# Sheet3.net
KiCad netlist of a schematic drawn in Altium Designer
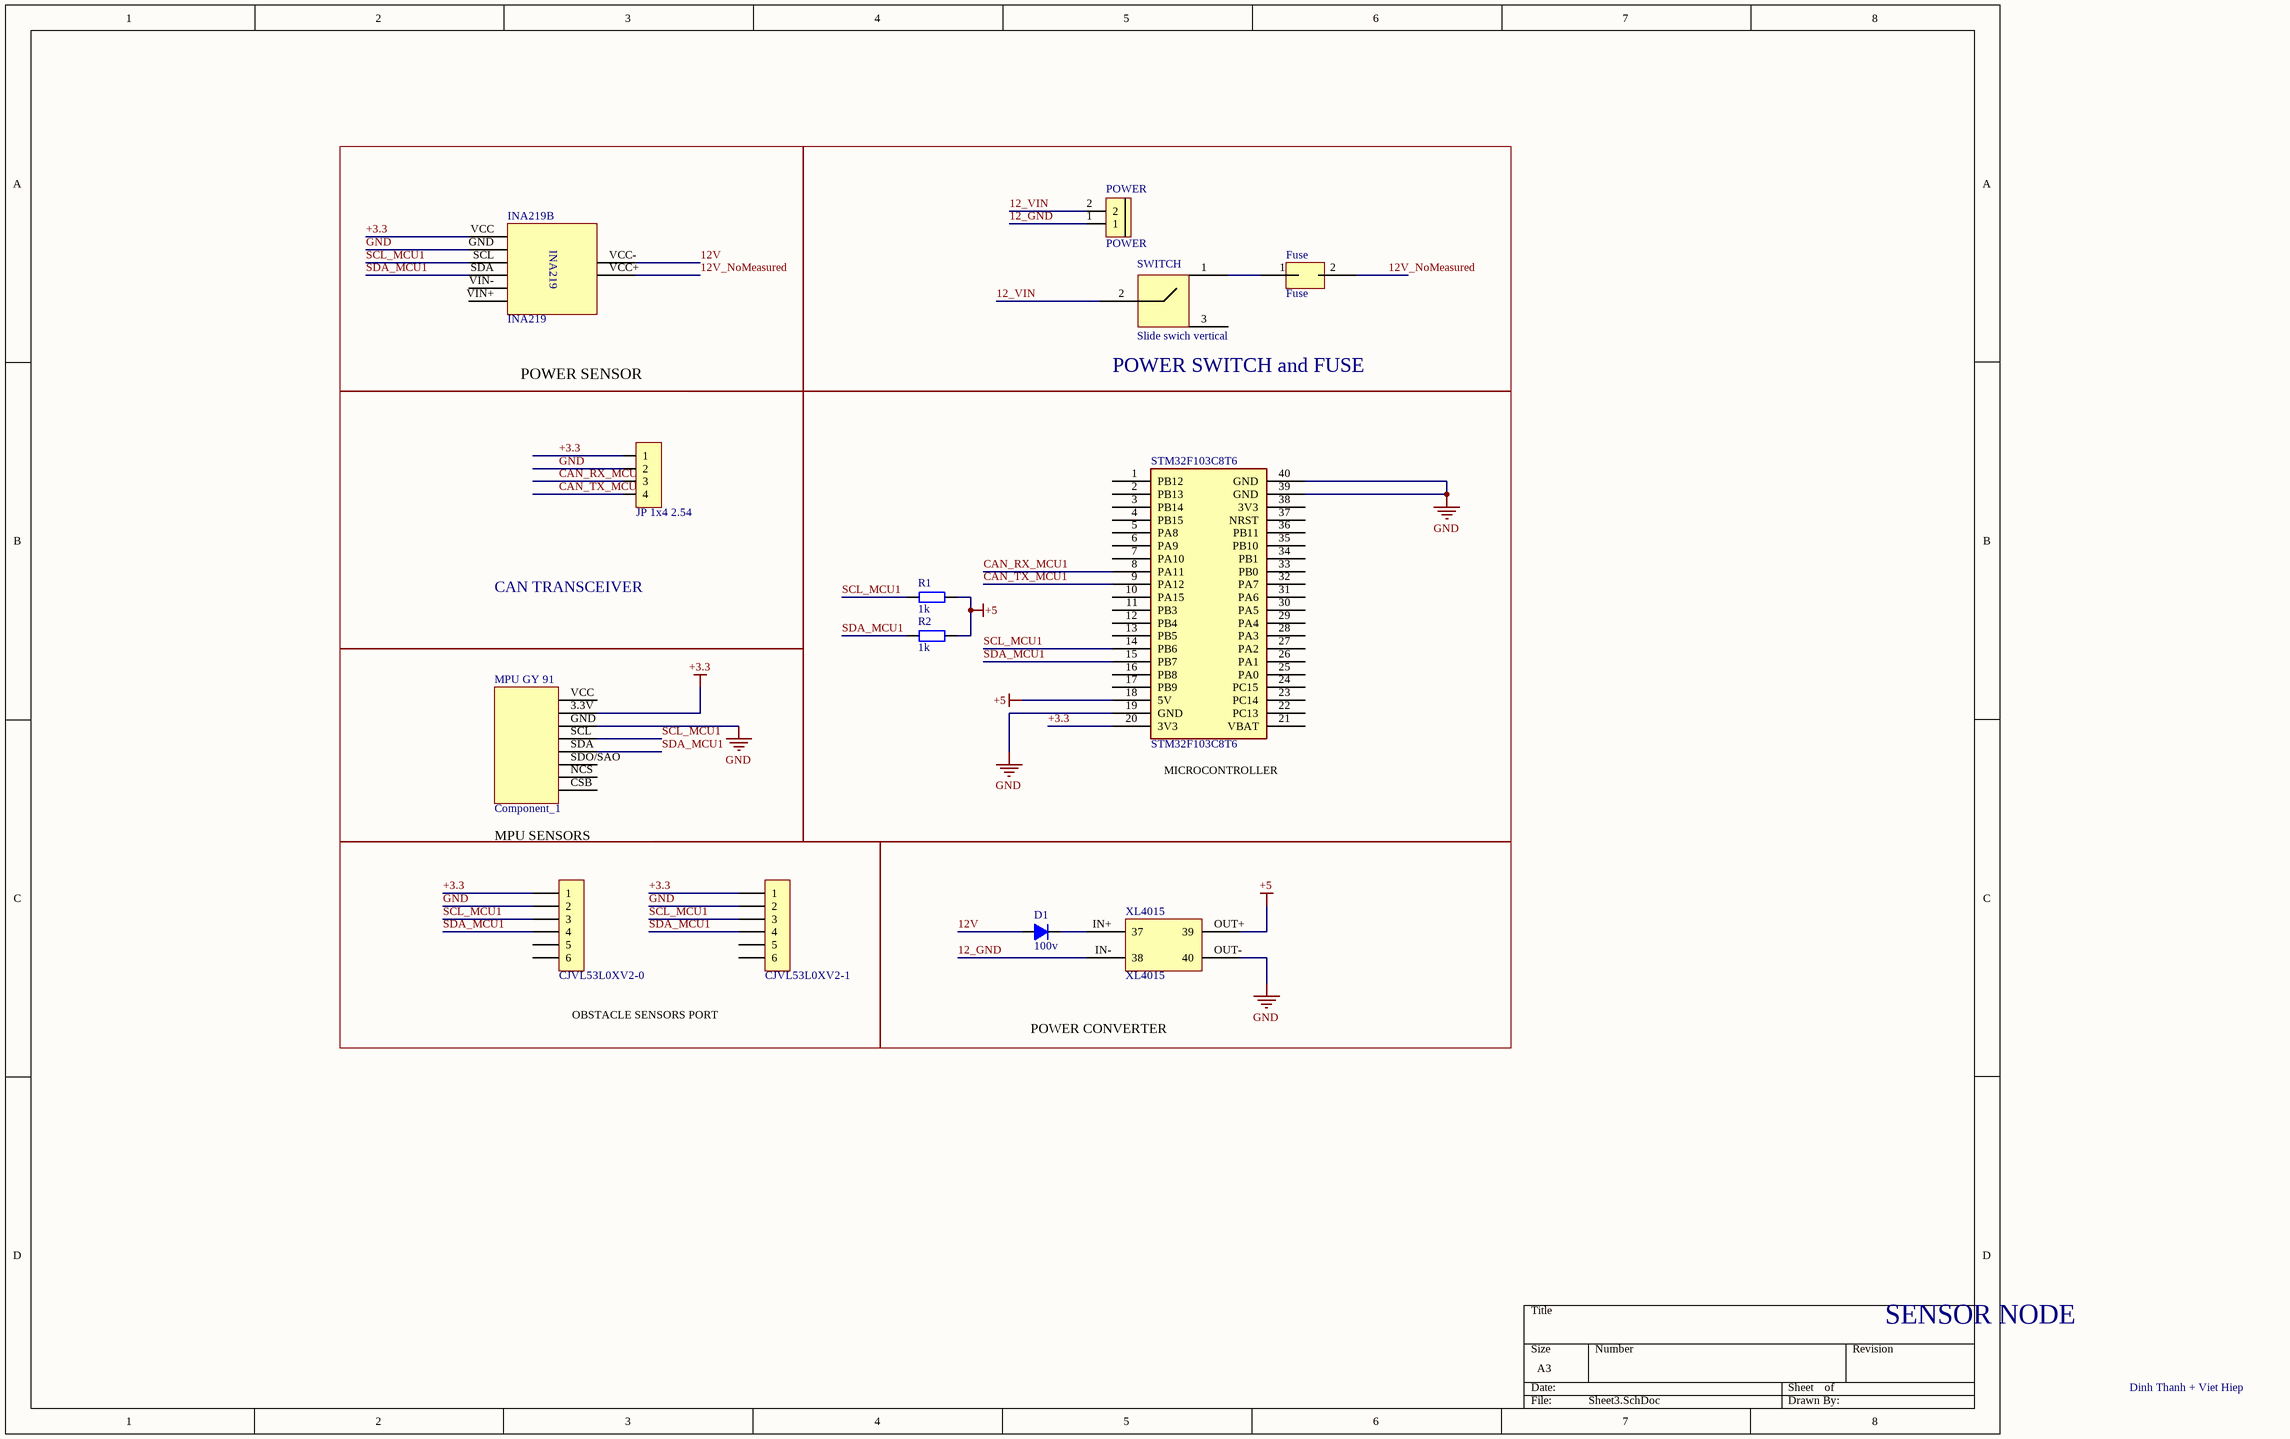
[diagram p0: Sheet3.SchDoc]

(export (version "E")
  (design (tool "Eeschema 10.0.6"))
  (components
    (comp (ref "CAN")
      (value "JP 1x4 2.54")
      (footprint "JP 1x4 CC")
      (description "Cắm")
      (libsource (lib "Jump") (part "JP 1x4 2.54 Cai Cong"))
    )
    (comp (ref "CJVL53L0XV2-0")
      (value "CJVL53L0XV2-0")
      (footprint "XH2.54M-6")
      (description "Cắm")
      (libsource (lib "Header") (part "Header 6P 2.54 Duc Thang"))
    )
    (comp (ref "CJVL53L0XV2-1")
      (value "CJVL53L0XV2-1")
      (footprint "XH2.54M-6")
      (description "Cắm")
      (libsource (lib "Header") (part "Header 6P 2.54 Duc Thang"))
    )
    (comp (ref "D1")
      (value "100v")
      (footprint "DIODE 1A")
      (description "Cắm")
      (libsource (lib "DIODE") (part "Diode 1N4007"))
    )
    (comp (ref "Fuse") (value "Fuse") (footprint "Fuse3") (libsource (lib "Fuse") (part "Fuse Holder 23mm")))
    (comp (ref "INA219") (value "INA219") (footprint "INA219") (libsource (lib "INA219") (part "INA219")))
    (comp (ref "MPU GY 91")
      (value "Component_1")
      (footprint "MPU GY 91")
      (libsource (lib "MPU GY01") (part "Component_1"))
    )
    (comp (ref "POWER")
      (value "POWER")
      (footprint "Con 2 KF301 5.08")
      (description "Cắm")
      (libsource (lib "Connector") (part "CON 2 KF301"))
    )
    (comp (ref "R1")
      (value "1k")
      (footprint "RES-SMD-1210")
      (description "Resistor R1/4W")
      (libsource (lib "Resistor") (part "R"))
    )
    (comp (ref "R2")
      (value "1k")
      (footprint "RES-SMD-1210")
      (description "Resistor R1/4W")
      (libsource (lib "Resistor") (part "R"))
    )
    (comp (ref "STM32F103C8T6")
      (value "STM32F103C8T6")
      (footprint "Stm32 BluePill")
      (description "Designed By @Alixahedi")
      (libsource (lib "Stm32 Blue Pill") (part "BluePill"))
    )
    (comp (ref "SWITCH")
      (value "Slide swich vertical")
      (footprint "SW102T")
      (libsource (lib "BUTTON-SWITCH") (part "Slide swich vertical"))
    )
    (comp (ref "XL4015") (value "XL4015") (footprint "XL4015") (libsource (lib "XL4015") (part "XL4015")))
  )
  (nets
    (net (code "1") (name "+3.3") (class "Default")
      (node (ref "CAN") (pin "1") (pinfunction "1_1") (pintype "passive"))
      (node (ref "CJVL53L0XV2-0") (pin "1") (pinfunction "1_1") (pintype "passive"))
      (node (ref "CJVL53L0XV2-1") (pin "1") (pinfunction "1_1") (pintype "passive"))
      (node (ref "INA219") (pin "VCC") (pinfunction "50_VCC") (pintype "passive"))
      (node (ref "MPU GY 91") (pin "3.3V") (pinfunction "3.3V_3.3V") (pintype "passive"))
      (node (ref "STM32F103C8T6") (pin "20") (pinfunction "3V3_20") (pintype "passive"))
    )
    (net (code "2") (name "+5") (class "Default")
      (node (ref "R1") (pin "2") (pinfunction "2_2") (pintype "passive"))
      (node (ref "R2") (pin "2") (pinfunction "2_2") (pintype "passive"))
      (node (ref "STM32F103C8T6") (pin "18") (pinfunction "5V_18") (pintype "passive"))
      (node (ref "XL4015") (pin "OUT+") (pinfunction "39_OUT+") (pintype "passive"))
    )
    (net (code "3") (name "/12V") (class "Default")
      (node (ref "D1") (pin "1") (pinfunction "A_1") (pintype "passive"))
      (node (ref "INA219") (pin "VCC-") (pinfunction "VIN-_VCC-") (pintype "passive"))
    )
    (net (code "4") (name "/12V_NoMeasured") (class "Default")
      (node (ref "Fuse") (pin "2") (pinfunction "46_2") (pintype "passive"))
      (node (ref "INA219") (pin "VCC+") (pintype "passive"))
    )
    (net (code "5") (name "/12_GND") (class "Default")
      (node (ref "POWER") (pin "1") (pinfunction "1_1") (pintype "passive"))
      (node (ref "XL4015") (pin "IN-") (pinfunction "38_IN-") (pintype "passive"))
    )
    (net (code "6") (name "/12_VIN") (class "Default")
      (node (ref "POWER") (pin "2") (pinfunction "2_2") (pintype "passive"))
      (node (ref "SWITCH") (pin "2") (pinfunction "41_2") (pintype "passive"))
    )
    (net (code "7") (name "/CAN_RX_MCU1") (class "Default")
      (node (ref "CAN") (pin "3") (pinfunction "3_3") (pintype "passive"))
      (node (ref "STM32F103C8T6") (pin "8") (pinfunction "PA11_8") (pintype "passive"))
    )
    (net (code "8") (name "/CAN_TX_MCU1") (class "Default")
      (node (ref "CAN") (pin "4") (pinfunction "4_4") (pintype "passive"))
      (node (ref "STM32F103C8T6") (pin "9") (pinfunction "PA12_9") (pintype "passive"))
    )
    (net (code "9") (name "/SCL_MCU1") (class "Default")
      (node (ref "CJVL53L0XV2-0") (pin "3") (pinfunction "3_3") (pintype "passive"))
      (node (ref "CJVL53L0XV2-1") (pin "3") (pinfunction "3_3") (pintype "passive"))
      (node (ref "INA219") (pin "SCL") (pinfunction "52_SCL") (pintype "passive"))
      (node (ref "MPU GY 91") (pin "SCL") (pinfunction "SCL_SCL") (pintype "passive"))
      (node (ref "R1") (pin "1") (pinfunction "1_1") (pintype "passive"))
      (node (ref "STM32F103C8T6") (pin "14") (pinfunction "PB6_14") (pintype "passive"))
    )
    (net (code "10") (name "/SDA_MCU1") (class "Default")
      (node (ref "CJVL53L0XV2-0") (pin "4") (pinfunction "4_4") (pintype "passive"))
      (node (ref "CJVL53L0XV2-1") (pin "4") (pinfunction "4_4") (pintype "passive"))
      (node (ref "INA219") (pin "SDA") (pinfunction "53_SDA") (pintype "passive"))
      (node (ref "MPU GY 91") (pin "SDA") (pinfunction "SDA_SDA") (pintype "passive"))
      (node (ref "R2") (pin "1") (pinfunction "1_1") (pintype "passive"))
      (node (ref "STM32F103C8T6") (pin "15") (pinfunction "PB7_15") (pintype "passive"))
    )
    (net (code "11") (name "GND") (class "Default")
      (node (ref "CAN") (pin "2") (pinfunction "2_2") (pintype "passive"))
      (node (ref "CJVL53L0XV2-0") (pin "2") (pinfunction "2_2") (pintype "passive"))
      (node (ref "CJVL53L0XV2-1") (pin "2") (pinfunction "2_2") (pintype "passive"))
      (node (ref "INA219") (pin "GND") (pinfunction "51_GND") (pintype "passive"))
      (node (ref "MPU GY 91") (pin "GND") (pinfunction "GND_GND") (pintype "passive"))
      (node (ref "STM32F103C8T6") (pin "19") (pinfunction "GND_19") (pintype "passive"))
      (node (ref "STM32F103C8T6") (pin "39") (pinfunction "GND_39") (pintype "passive"))
      (node (ref "STM32F103C8T6") (pin "40") (pinfunction "GND_40") (pintype "passive"))
      (node (ref "XL4015") (pin "OUT-") (pinfunction "40_OUT-") (pintype "passive"))
    )
    (net (code "12") (name "Net-(D1-K)") (class "Default")
      (node (ref "D1") (pin "2") (pinfunction "K_2") (pintype "passive"))
      (node (ref "XL4015") (pin "IN+") (pinfunction "37_IN+") (pintype "passive"))
    )
    (net (code "13") (name "Net-(Fuse-45)") (class "Default")
      (node (ref "Fuse") (pin "1") (pinfunction "45_1") (pintype "passive"))
      (node (ref "SWITCH") (pin "1") (pinfunction "42_1") (pintype "passive"))
    )
    (net (code "14") (name "unconnected-(CJVL53L0XV2-0-Pad5)") (class "Default")
      (node (ref "CJVL53L0XV2-0") (pin "5") (pinfunction "5_5") (pintype "passive"))
    )
    (net (code "15") (name "unconnected-(CJVL53L0XV2-0-Pad6)") (class "Default")
      (node (ref "CJVL53L0XV2-0") (pin "6") (pinfunction "6_6") (pintype "passive"))
    )
    (net (code "16") (name "unconnected-(CJVL53L0XV2-1-Pad5)") (class "Default")
      (node (ref "CJVL53L0XV2-1") (pin "5") (pinfunction "5_5") (pintype "passive"))
    )
    (net (code "17") (name "unconnected-(CJVL53L0XV2-1-Pad6)") (class "Default")
      (node (ref "CJVL53L0XV2-1") (pin "6") (pinfunction "6_6") (pintype "passive"))
    )
    (net (code "18") (name "unconnected-(INA219B-54-PadVIN-)") (class "Default")
      (node (ref "INA219") (pin "VIN-") (pinfunction "54_VIN-") (pintype "passive"))
    )
    (net (code "19") (name "unconnected-(INA219B-55-PadVIN+)") (class "Default")
      (node (ref "INA219") (pin "VIN+") (pinfunction "55_VIN+") (pintype "passive"))
    )
    (net (code "20") (name "unconnected-(MPU GY 91-PadCSB)") (class "Default")
      (node (ref "MPU GY 91") (pin "CSB") (pinfunction "CSB_CSB") (pintype "passive"))
    )
    (net (code "21") (name "unconnected-(MPU GY 91-PadNCS)") (class "Default")
      (node (ref "MPU GY 91") (pin "NCS") (pinfunction "NCS_NCS") (pintype "passive"))
    )
    (net (code "22") (name "unconnected-(MPU GY 91-PadSDO{slash}SAO)") (class "Default")
      (node (ref "MPU GY 91") (pin "SDO/SAO") (pinfunction "SDO/SAO_SDO/SAO") (pintype "passive"))
    )
    (net (code "23") (name "unconnected-(MPU GY 91-PadVCC)") (class "Default")
      (node (ref "MPU GY 91") (pin "VCC") (pinfunction "VCC_VCC") (pintype "passive"))
    )
    (net (code "24") (name "unconnected-(STM32F103C8T6-3V3-Pad38)") (class "Default")
      (node (ref "STM32F103C8T6") (pin "38") (pinfunction "3V3_38") (pintype "passive"))
    )
    (net (code "25") (name "unconnected-(STM32F103C8T6-NRST-Pad37)") (class "Default")
      (node (ref "STM32F103C8T6") (pin "37") (pinfunction "NRST_37") (pintype "passive"))
    )
    (net (code "26") (name "unconnected-(STM32F103C8T6-PA0-Pad25)") (class "Default")
      (node (ref "STM32F103C8T6") (pin "25") (pinfunction "PA0_25") (pintype "passive"))
    )
    (net (code "27") (name "unconnected-(STM32F103C8T6-PA1-Pad26)") (class "Default")
      (node (ref "STM32F103C8T6") (pin "26") (pinfunction "PA1_26") (pintype "passive"))
    )
    (net (code "28") (name "unconnected-(STM32F103C8T6-PA2-Pad27)") (class "Default")
      (node (ref "STM32F103C8T6") (pin "27") (pinfunction "PA2_27") (pintype "passive"))
    )
    (net (code "29") (name "unconnected-(STM32F103C8T6-PA3-Pad28)") (class "Default")
      (node (ref "STM32F103C8T6") (pin "28") (pinfunction "PA3_28") (pintype "passive"))
    )
    (net (code "30") (name "unconnected-(STM32F103C8T6-PA4-Pad29)") (class "Default")
      (node (ref "STM32F103C8T6") (pin "29") (pinfunction "PA4_29") (pintype "passive"))
    )
    (net (code "31") (name "unconnected-(STM32F103C8T6-PA5-Pad30)") (class "Default")
      (node (ref "STM32F103C8T6") (pin "30") (pinfunction "PA5_30") (pintype "passive"))
    )
    (net (code "32") (name "unconnected-(STM32F103C8T6-PA6-Pad31)") (class "Default")
      (node (ref "STM32F103C8T6") (pin "31") (pinfunction "PA6_31") (pintype "passive"))
    )
    (net (code "33") (name "unconnected-(STM32F103C8T6-PA7-Pad32)") (class "Default")
      (node (ref "STM32F103C8T6") (pin "32") (pinfunction "PA7_32") (pintype "passive"))
    )
    (net (code "34") (name "unconnected-(STM32F103C8T6-PA8-Pad5)") (class "Default")
      (node (ref "STM32F103C8T6") (pin "5") (pinfunction "PA8_5") (pintype "passive"))
    )
    (net (code "35") (name "unconnected-(STM32F103C8T6-PA9-Pad6)") (class "Default")
      (node (ref "STM32F103C8T6") (pin "6") (pinfunction "PA9_6") (pintype "passive"))
    )
    (net (code "36") (name "unconnected-(STM32F103C8T6-PA10-Pad7)") (class "Default")
      (node (ref "STM32F103C8T6") (pin "7") (pinfunction "PA10_7") (pintype "passive"))
    )
    (net (code "37") (name "unconnected-(STM32F103C8T6-PA15-Pad10)") (class "Default")
      (node (ref "STM32F103C8T6") (pin "10") (pinfunction "PA15_10") (pintype "passive"))
    )
    (net (code "38") (name "unconnected-(STM32F103C8T6-PB0-Pad33)") (class "Default")
      (node (ref "STM32F103C8T6") (pin "33") (pinfunction "PB0_33") (pintype "passive"))
    )
    (net (code "39") (name "unconnected-(STM32F103C8T6-PB1-Pad34)") (class "Default")
      (node (ref "STM32F103C8T6") (pin "34") (pinfunction "PB1_34") (pintype "passive"))
    )
    (net (code "40") (name "unconnected-(STM32F103C8T6-PB3-Pad11)") (class "Default")
      (node (ref "STM32F103C8T6") (pin "11") (pinfunction "PB3_11") (pintype "passive"))
    )
    (net (code "41") (name "unconnected-(STM32F103C8T6-PB4-Pad12)") (class "Default")
      (node (ref "STM32F103C8T6") (pin "12") (pinfunction "PB4_12") (pintype "passive"))
    )
    (net (code "42") (name "unconnected-(STM32F103C8T6-PB5-Pad13)") (class "Default")
      (node (ref "STM32F103C8T6") (pin "13") (pinfunction "PB5_13") (pintype "passive"))
    )
    (net (code "43") (name "unconnected-(STM32F103C8T6-PB8-Pad16)") (class "Default")
      (node (ref "STM32F103C8T6") (pin "16") (pinfunction "PB8_16") (pintype "passive"))
    )
    (net (code "44") (name "unconnected-(STM32F103C8T6-PB9-Pad17)") (class "Default")
      (node (ref "STM32F103C8T6") (pin "17") (pinfunction "PB9_17") (pintype "passive"))
    )
    (net (code "45") (name "unconnected-(STM32F103C8T6-PB10-Pad35)") (class "Default")
      (node (ref "STM32F103C8T6") (pin "35") (pinfunction "PB10_35") (pintype "passive"))
    )
    (net (code "46") (name "unconnected-(STM32F103C8T6-PB11-Pad36)") (class "Default")
      (node (ref "STM32F103C8T6") (pin "36") (pinfunction "PB11_36") (pintype "passive"))
    )
    (net (code "47") (name "unconnected-(STM32F103C8T6-PB12-Pad1)") (class "Default")
      (node (ref "STM32F103C8T6") (pin "1") (pinfunction "PB12_1") (pintype "passive"))
    )
    (net (code "48") (name "unconnected-(STM32F103C8T6-PB13-Pad2)") (class "Default")
      (node (ref "STM32F103C8T6") (pin "2") (pinfunction "PB13_2") (pintype "passive"))
    )
    (net (code "49") (name "unconnected-(STM32F103C8T6-PB14-Pad3)") (class "Default")
      (node (ref "STM32F103C8T6") (pin "3") (pinfunction "PB14_3") (pintype "passive"))
    )
    (net (code "50") (name "unconnected-(STM32F103C8T6-PB15-Pad4)") (class "Default")
      (node (ref "STM32F103C8T6") (pin "4") (pinfunction "PB15_4") (pintype "passive"))
    )
    (net (code "51") (name "unconnected-(STM32F103C8T6-PC13-Pad22)") (class "Default")
      (node (ref "STM32F103C8T6") (pin "22") (pinfunction "PC13_22") (pintype "passive"))
    )
    (net (code "52") (name "unconnected-(STM32F103C8T6-PC14-Pad23)") (class "Default")
      (node (ref "STM32F103C8T6") (pin "23") (pinfunction "PC14_23") (pintype "passive"))
    )
    (net (code "53") (name "unconnected-(STM32F103C8T6-PC15-Pad24)") (class "Default")
      (node (ref "STM32F103C8T6") (pin "24") (pinfunction "PC15_24") (pintype "passive"))
    )
    (net (code "54") (name "unconnected-(STM32F103C8T6-VBAT-Pad21)") (class "Default")
      (node (ref "STM32F103C8T6") (pin "21") (pinfunction "VBAT_21") (pintype "passive"))
    )
    (net (code "55") (name "unconnected-(SWITCH-43-Pad3)") (class "Default")
      (node (ref "SWITCH") (pin "3") (pinfunction "43_3") (pintype "passive"))
    )
  )
)
